# 2DD-17-mk-2_3.net
KiCad netlist of a schematic drawn in EAGLE
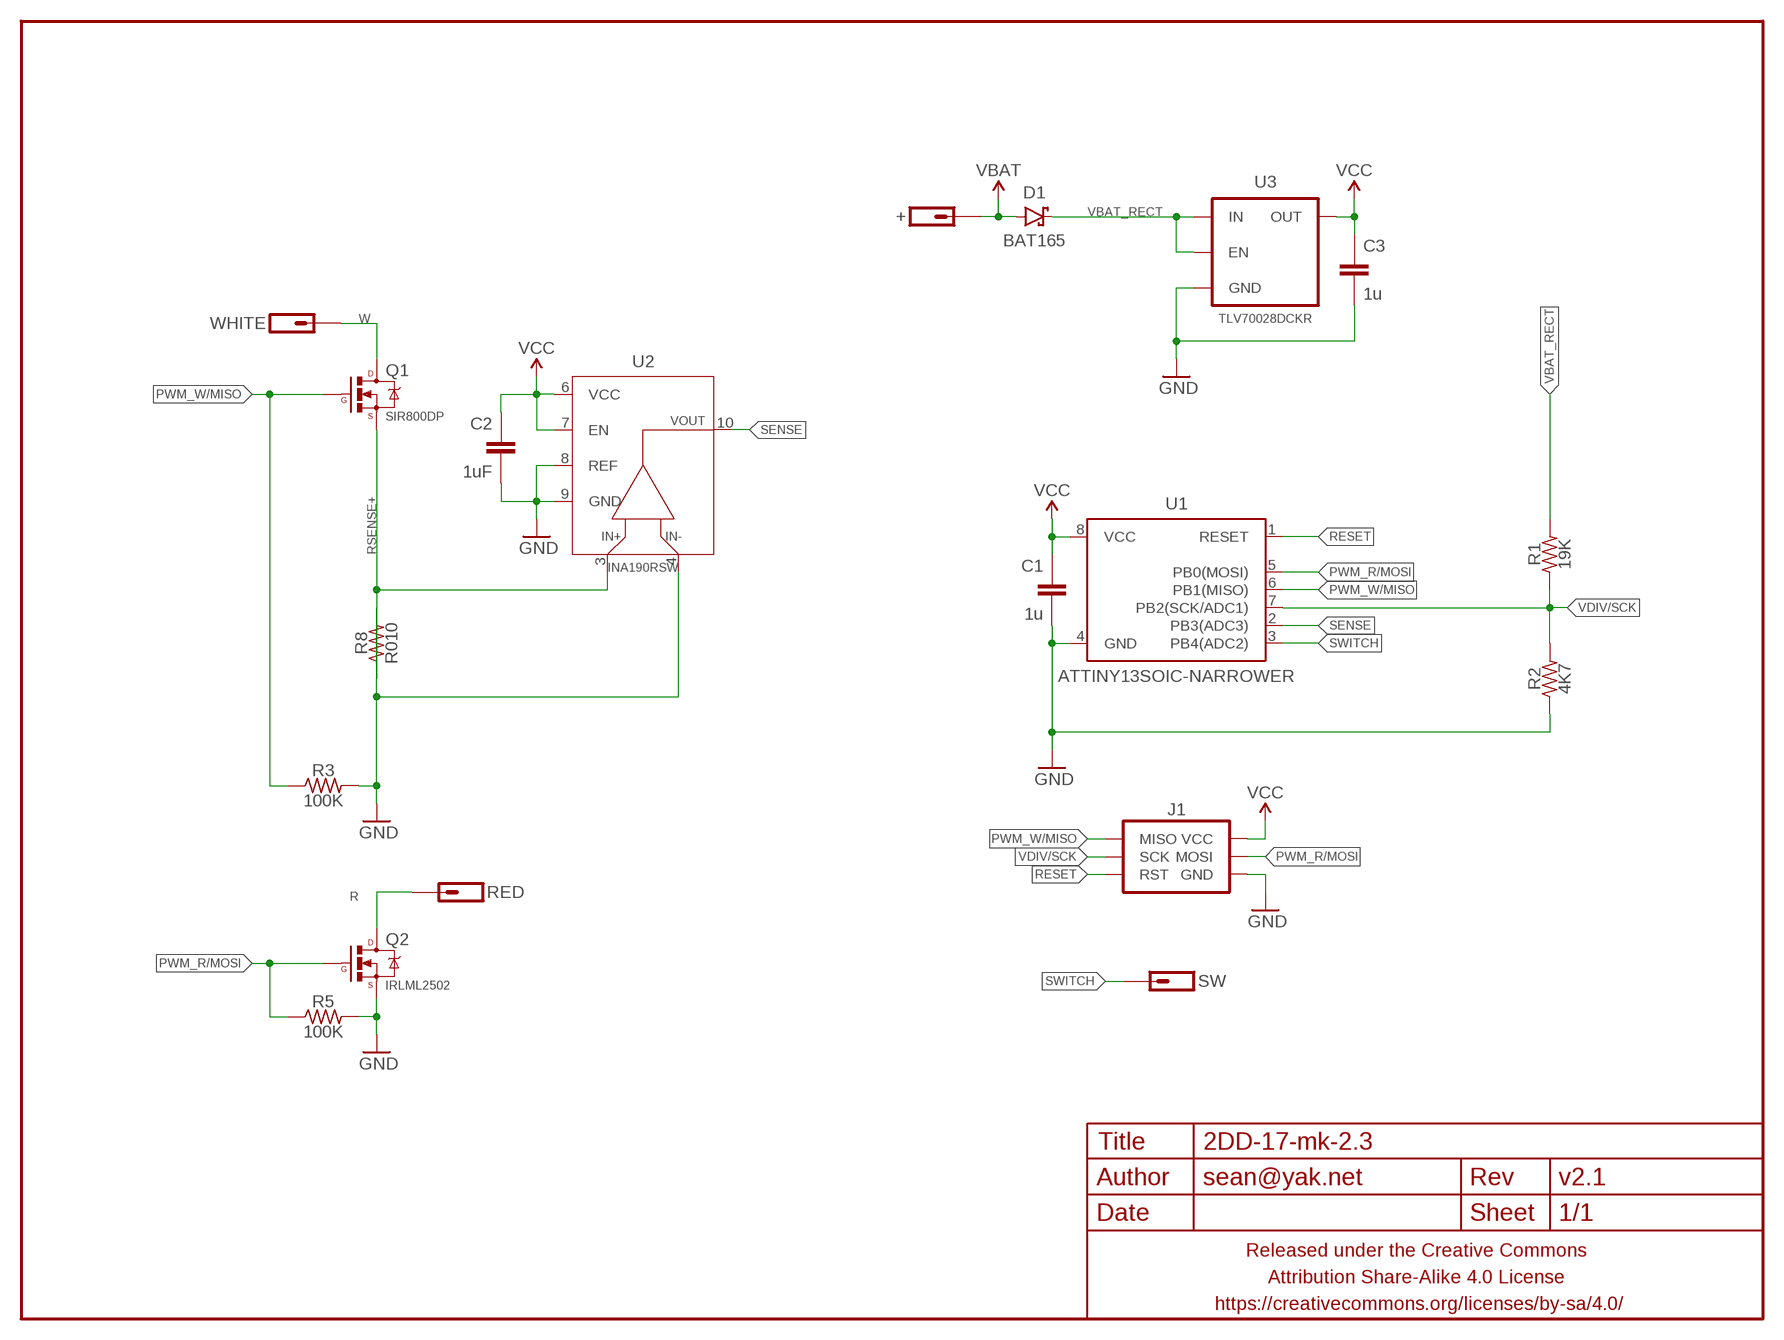
[diagram p0: schematic, sheet 1]

(export (version "E")
  (design (tool "Eeschema 10.0.6"))
  (components
    (comp (ref "+")
      (value "M01PTH-1MM-CIR-NS")
      (footprint "eagle-import:1X01-1MM-CIR-NS")
      (libsource (lib "eagle-import") (part "M01PTH-1MM-CIR-NS"))
    )
    (comp (ref "C1")
      (value "1u")
      (footprint "eagle-import:C0402")
      (libsource (lib "eagle-import") (part "CAPACITOR-CERAMICC0402"))
    )
    (comp (ref "C2")
      (value "1uF")
      (footprint "eagle-import:C0402")
      (libsource (lib "eagle-import") (part "CAPACITOR-CERAMICC0402"))
    )
    (comp (ref "C3")
      (value "1u")
      (footprint "eagle-import:C0402")
      (libsource (lib "eagle-import") (part "CAPACITOR-CERAMICC0402"))
    )
    (comp (ref "D1")
      (value "BAT165")
      (footprint "eagle-import:SOD323-SCHOTTKY")
      (libsource (lib "eagle-import") (part "DIODE-SCHOTTKYSOD323"))
    )
    (comp (ref "FRAME1")
      (value "FRAME-LETTERNO_PACKAGE")
      (footprint "eagle-import:DUMMY")
      (fields
        (field (name "DESIGNER") "Nobody")
        (field (name "VERSION") "v01")
        (field (name "DESIGNER_1") "sean@yak.net")
        (field (name "VERSION_1") "v2.1")
      )
      (libsource (lib "eagle-import") (part "FRAME-LETTERNO_PACKAGE"))
    )
    (comp (ref "J1")
      (value "AVR_SPI_PRG_6SMD-1.27MM")
      (footprint "eagle-import:2X3-1.27MM-SMD")
      (libsource (lib "eagle-import") (part "AVR_SPI_PRG_6SMD-1.27MM"))
    )
    (comp (ref "Q1")
      (value "SIR800DP")
      (footprint "eagle-import:LFPAK56")
      (libsource (lib "eagle-import") (part "MOSFET-NCHANNELPSMN4R0-30YLD"))
    )
    (comp (ref "Q2")
      (value "IRLML2502")
      (footprint "eagle-import:SOT23")
      (libsource (lib "eagle-import") (part "MOSFET-NCHANNELIRLML2502"))
    )
    (comp (ref "R1")
      (value "19K")
      (footprint "eagle-import:R0402")
      (libsource (lib "eagle-import") (part "RESISTORR0402"))
    )
    (comp (ref "R2")
      (value "4K7")
      (footprint "eagle-import:R0402")
      (libsource (lib "eagle-import") (part "RESISTORR0402"))
    )
    (comp (ref "R3")
      (value "100K")
      (footprint "eagle-import:R0402")
      (libsource (lib "eagle-import") (part "RESISTORR0402"))
    )
    (comp (ref "R5")
      (value "100K")
      (footprint "eagle-import:R0402")
      (libsource (lib "eagle-import") (part "RESISTORR0402"))
    )
    (comp (ref "R8")
      (value "R010")
      (footprint "eagle-import:R1206")
      (libsource (lib "eagle-import") (part "RESISTORR1206"))
    )
    (comp (ref "RED")
      (value "M01SMD-1.25MM-DIA")
      (footprint "eagle-import:1X01-SMD-1.25DIA")
      (libsource (lib "eagle-import") (part "M01SMD-1.25MM-DIA"))
    )
    (comp (ref "SW")
      (value "M01SMD-1.25MM-DIA")
      (footprint "eagle-import:1X01-SMD-1.25DIA")
      (libsource (lib "eagle-import") (part "M01SMD-1.25MM-DIA"))
    )
    (comp (ref "U1")
      (value "ATTINY13SOIC-NARROWER")
      (footprint "eagle-import:SO08-SKINNYPADS")
      (libsource (lib "eagle-import") (part "ATTINY13SOIC-NARROWER"))
    )
    (comp (ref "U2")
      (value "INA190RSW")
      (footprint "eagle-import:UQFN-10")
      (libsource (lib "eagle-import") (part "INA190RSW"))
    )
    (comp (ref "U3")
      (value "TLV70028DCKR")
      (footprint "eagle-import:SC70")
      (libsource (lib "eagle-import") (part "V_REG_ENTLV700XXDCR"))
    )
    (comp (ref "WHITE")
      (value "M01SMD-1.25MM-DIA")
      (footprint "eagle-import:1X01-SMD-1.25DIA")
      (libsource (lib "eagle-import") (part "M01SMD-1.25MM-DIA"))
    )
  )
  (nets
    (net (code "1") (name "/R") (class "Default")
      (node (ref "Q2") (pin "3") (pinfunction "D_3") (pintype "passive"))
      (node (ref "RED") (pin "P$1") (pinfunction "1_P$1") (pintype "passive"))
    )
    (net (code "2") (name "/RSENSE+") (class "Default")
      (node (ref "Q1") (pin "1") (pinfunction "S_1") (pintype "passive"))
      (node (ref "Q1") (pin "2") (pinfunction "S_2") (pintype "passive"))
      (node (ref "Q1") (pin "3") (pinfunction "S_3") (pintype "passive"))
      (node (ref "R8") (pin "1") (pinfunction "1_1") (pintype "passive"))
      (node (ref "U2") (pin "3") (pinfunction "VIN+_3") (pintype "bidirectional"))
    )
    (net (code "3") (name "/W") (class "Default")
      (node (ref "Q1") (pin "PAD") (pinfunction "D_PAD") (pintype "passive"))
      (node (ref "WHITE") (pin "P$1") (pinfunction "1_P$1") (pintype "passive"))
    )
    (net (code "4") (name "GND") (class "Default")
      (node (ref "C1") (pin "2") (pinfunction "2_2") (pintype "passive"))
      (node (ref "C2") (pin "2") (pinfunction "2_2") (pintype "passive"))
      (node (ref "C3") (pin "2") (pinfunction "2_2") (pintype "passive"))
      (node (ref "J1") (pin "6") (pinfunction "GND_6") (pintype "passive"))
      (node (ref "Q2") (pin "2") (pinfunction "S_2") (pintype "passive"))
      (node (ref "R2") (pin "1") (pinfunction "1_1") (pintype "passive"))
      (node (ref "R3") (pin "2") (pinfunction "2_2") (pintype "passive"))
      (node (ref "R5") (pin "2") (pinfunction "2_2") (pintype "passive"))
      (node (ref "R8") (pin "2") (pinfunction "2_2") (pintype "passive"))
      (node (ref "U1") (pin "4") (pinfunction "GND_4") (pintype "bidirectional"))
      (node (ref "U2") (pin "4") (pinfunction "VIN-_4") (pintype "bidirectional"))
      (node (ref "U2") (pin "8") (pinfunction "REF_8") (pintype "bidirectional"))
      (node (ref "U2") (pin "9") (pinfunction "GND_9") (pintype "bidirectional"))
      (node (ref "U3") (pin "2") (pinfunction "GND_2") (pintype "input"))
    )
    (net (code "5") (name "PWM_R{slash}MOSI") (class "Default")
      (node (ref "J1") (pin "4") (pinfunction "MOSI_4") (pintype "passive"))
      (node (ref "Q2") (pin "1") (pinfunction "G_1") (pintype "passive"))
      (node (ref "R5") (pin "1") (pinfunction "1_1") (pintype "passive"))
      (node (ref "U1") (pin "5") (pinfunction "PB0(MOSI)_5") (pintype "bidirectional"))
    )
    (net (code "6") (name "PWM_W{slash}MISO") (class "Default")
      (node (ref "J1") (pin "1") (pinfunction "MISO_1") (pintype "passive"))
      (node (ref "Q1") (pin "4") (pinfunction "G_4") (pintype "passive"))
      (node (ref "R3") (pin "1") (pinfunction "1_1") (pintype "passive"))
      (node (ref "U1") (pin "6") (pinfunction "PB1(MISO)_6") (pintype "bidirectional"))
    )
    (net (code "7") (name "RESET") (class "Default")
      (node (ref "J1") (pin "5") (pinfunction "RST_5") (pintype "passive"))
      (node (ref "U1") (pin "1") (pinfunction "RESET_1") (pintype "bidirectional"))
    )
    (net (code "8") (name "SENSE") (class "Default")
      (node (ref "U1") (pin "2") (pinfunction "PB3(ADC3)_2") (pintype "bidirectional"))
      (node (ref "U2") (pin "10") (pinfunction "OUT_10") (pintype "bidirectional"))
    )
    (net (code "9") (name "SWITCH") (class "Default")
      (node (ref "SW") (pin "P$1") (pinfunction "1_P$1") (pintype "passive"))
      (node (ref "U1") (pin "3") (pinfunction "PB4(ADC2)_3") (pintype "bidirectional"))
    )
    (net (code "10") (name "VBAT") (class "Default")
      (node (ref "+") (pin "1") (pinfunction "1_1") (pintype "passive"))
      (node (ref "D1") (pin "A") (pinfunction "A_A") (pintype "passive"))
    )
    (net (code "11") (name "VBAT_RECT") (class "Default")
      (node (ref "D1") (pin "C") (pinfunction "C_C") (pintype "passive"))
      (node (ref "R1") (pin "2") (pinfunction "2_2") (pintype "passive"))
      (node (ref "U3") (pin "1") (pinfunction "IN_1") (pintype "input"))
      (node (ref "U3") (pin "3") (pinfunction "EN_3") (pintype "input"))
    )
    (net (code "12") (name "VCC") (class "Default")
      (node (ref "C1") (pin "1") (pinfunction "1_1") (pintype "passive"))
      (node (ref "C2") (pin "1") (pinfunction "1_1") (pintype "passive"))
      (node (ref "C3") (pin "1") (pinfunction "1_1") (pintype "passive"))
      (node (ref "J1") (pin "2") (pinfunction "VCC_2") (pintype "passive"))
      (node (ref "U1") (pin "8") (pinfunction "VCC_8") (pintype "bidirectional"))
      (node (ref "U2") (pin "6") (pinfunction "VCC_6") (pintype "bidirectional"))
      (node (ref "U2") (pin "7") (pinfunction "EN_7") (pintype "bidirectional"))
      (node (ref "U3") (pin "5") (pinfunction "OUT_5") (pintype "passive"))
    )
    (net (code "13") (name "VDIV{slash}SCK") (class "Default")
      (node (ref "J1") (pin "3") (pinfunction "SCK_3") (pintype "passive"))
      (node (ref "R1") (pin "1") (pinfunction "1_1") (pintype "passive"))
      (node (ref "R2") (pin "2") (pinfunction "2_2") (pintype "passive"))
      (node (ref "U1") (pin "7") (pinfunction "PB2(SCK/ADC1)_7") (pintype "bidirectional"))
    )
  )
)
